# Magic_Panel_I2C_Interface.net
KiCad netlist of a schematic drawn in EAGLE
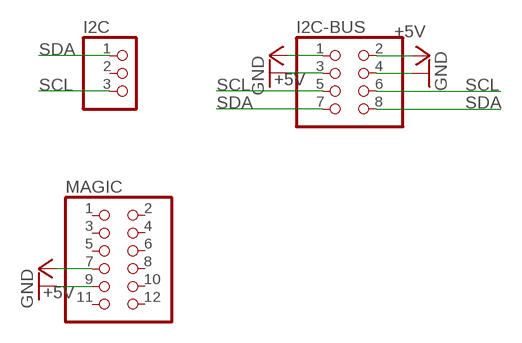
[diagram p0: schematic, sheet 1]

(export (version "E")
  (design (tool "Eeschema 10.0.6"))
  (components
    (comp (ref "I2C")
      (value "PINHD-1X3CB")
      (footprint "eagle-import:1X03-CLEANBIG")
      (libsource (lib "eagle-import") (part "PINHD-1X3CB"))
    )
    (comp (ref "I2C-BUS")
      (value "PINHD-2X4")
      (footprint "eagle-import:2X04")
      (libsource (lib "eagle-import") (part "PINHD-2X4"))
    )
    (comp (ref "MAGIC")
      (value "PINHD-2X6")
      (footprint "eagle-import:2X06")
      (libsource (lib "eagle-import") (part "PINHD-2X6"))
    )
  )
  (nets
    (net (code "1") (name "+5V") (class "Default")
      (node (ref "I2C-BUS") (pin "1") (pinfunction "1_1") (pintype "passive"))
      (node (ref "I2C-BUS") (pin "2") (pinfunction "2_2") (pintype "passive"))
      (node (ref "MAGIC") (pin "7") (pinfunction "7_7") (pintype "passive"))
    )
    (net (code "2") (name "/SCL") (class "Default")
      (node (ref "I2C") (pin "3") (pinfunction "3_3") (pintype "passive"))
      (node (ref "I2C-BUS") (pin "5") (pinfunction "5_5") (pintype "passive"))
      (node (ref "I2C-BUS") (pin "6") (pinfunction "6_6") (pintype "passive"))
    )
    (net (code "3") (name "/SDA") (class "Default")
      (node (ref "I2C") (pin "1") (pinfunction "1_1") (pintype "passive"))
      (node (ref "I2C-BUS") (pin "7") (pinfunction "7_7") (pintype "passive"))
      (node (ref "I2C-BUS") (pin "8") (pinfunction "8_8") (pintype "passive"))
    )
    (net (code "4") (name "GND") (class "Default")
      (node (ref "I2C-BUS") (pin "3") (pinfunction "3_3") (pintype "passive"))
      (node (ref "I2C-BUS") (pin "4") (pinfunction "4_4") (pintype "passive"))
      (node (ref "MAGIC") (pin "9") (pinfunction "9_9") (pintype "passive"))
    )
    (net (code "5") (name "unconnected-(I2C-Pad2)") (class "Default")
      (node (ref "I2C") (pin "2") (pinfunction "2_2") (pintype "passive"))
    )
    (net (code "6") (name "unconnected-(MAGIC-Pad1)") (class "Default")
      (node (ref "MAGIC") (pin "1") (pinfunction "1_1") (pintype "passive"))
    )
    (net (code "7") (name "unconnected-(MAGIC-Pad2)") (class "Default")
      (node (ref "MAGIC") (pin "2") (pinfunction "2_2") (pintype "passive"))
    )
    (net (code "8") (name "unconnected-(MAGIC-Pad3)") (class "Default")
      (node (ref "MAGIC") (pin "3") (pinfunction "3_3") (pintype "passive"))
    )
    (net (code "9") (name "unconnected-(MAGIC-Pad4)") (class "Default")
      (node (ref "MAGIC") (pin "4") (pinfunction "4_4") (pintype "passive"))
    )
    (net (code "10") (name "unconnected-(MAGIC-Pad5)") (class "Default")
      (node (ref "MAGIC") (pin "5") (pinfunction "5_5") (pintype "passive"))
    )
    (net (code "11") (name "unconnected-(MAGIC-Pad6)") (class "Default")
      (node (ref "MAGIC") (pin "6") (pinfunction "6_6") (pintype "passive"))
    )
    (net (code "12") (name "unconnected-(MAGIC-Pad8)") (class "Default")
      (node (ref "MAGIC") (pin "8") (pinfunction "8_8") (pintype "passive"))
    )
    (net (code "13") (name "unconnected-(MAGIC-Pad10)") (class "Default")
      (node (ref "MAGIC") (pin "10") (pinfunction "10_10") (pintype "passive"))
    )
    (net (code "14") (name "unconnected-(MAGIC-Pad11)") (class "Default")
      (node (ref "MAGIC") (pin "11") (pinfunction "11_11") (pintype "passive"))
    )
    (net (code "15") (name "unconnected-(MAGIC-Pad12)") (class "Default")
      (node (ref "MAGIC") (pin "12") (pinfunction "12_12") (pintype "passive"))
    )
  )
)
